# NFC.net
KiCad netlist of a schematic drawn in Altium Designer
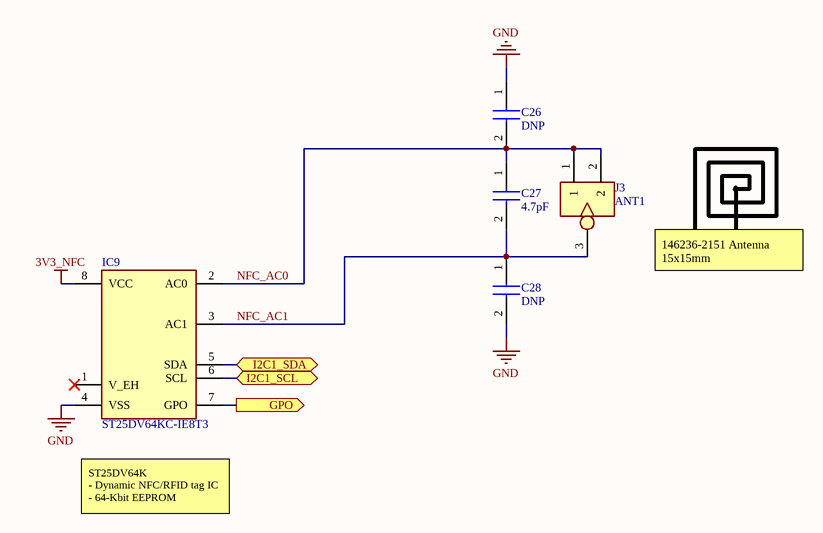
[diagram p0: NFC.SchDoc]

(export (version "E")
  (design (tool "Eeschema 10.0.6"))
  (components
    (comp (ref "C26")
      (value "DNP")
      (footprint "SamacSys:CAPC1005X70N")
      (description "Capacitor")
      (fields
        (field (name "MANUFACTURER_PART_NUMBER") "GRM1555C2A4R7WA01D")
        (field (name "MOUSER PART NUMBER") "81-GRM1555C2A4R7WA1D")
      )
      (libsource (lib "*") (part "GRM1555C2A4R7WA01D"))
    )
    (comp (ref "C27")
      (value "4.7pF")
      (footprint "SamacSys:CAPC1005X70N")
      (description "Capacitor")
      (fields
        (field (name "MANUFACTURER_PART_NUMBER") "GRM1555C2A4R7WA01D")
        (field (name "MOUSER PART NUMBER") "81-GRM1555C2A4R7WA1D")
      )
      (libsource (lib "*") (part "GRM1555C2A4R7WA01D"))
    )
    (comp (ref "C28")
      (value "DNP")
      (footprint "SamacSys:CAPC1005X70N")
      (description "Capacitor")
      (fields
        (field (name "MANUFACTURER_PART_NUMBER") "GRM1555C2A4R7WA01D")
        (field (name "MOUSER PART NUMBER") "81-GRM1555C2A4R7WA1D")
      )
      (libsource (lib "*") (part "GRM1555C2A4R7WA01D"))
    )
    (comp (ref "IC9")
      (value "ST25DV64KC-IE8T3")
      (footprint "SamacSys:SOP65P640X120-8N")
      (description "Integrated Circuit")
      (fields (field (name "MOUSER PART NUMBER") "511-ST25DV64KC-IE8T3"))
      (libsource (lib "SamacSys") (part "ST25DV64KC-IE8T3"))
    )
    (comp (ref "J3")
      (value "ANT1")
      (footprint "SamacSys:RECE.20279.001E.01")
      (description "Connector")
      (fields (field (name "MANUFACTURER_PART_NUMBER") "RECE-20279-001E-01"))
      (libsource (lib "SamacSys") (part "RECE-20279-001E-01"))
    )
  )
  (nets
    (net (code "1") (name "/GPO") (class "Default")
      (node (ref "IC9") (pin "7") (pinfunction "GPO_7") (pintype "open_collector"))
    )
    (net (code "2") (name "/I2C1_SCL") (class "Default")
      (node (ref "IC9") (pin "6") (pinfunction "SCL_6") (pintype "passive"))
    )
    (net (code "3") (name "/I2C1_SDA") (class "Default")
      (node (ref "IC9") (pin "5") (pinfunction "SDA_5") (pintype "passive"))
    )
    (net (code "4") (name "/NFC_AC0") (class "Default")
      (node (ref "C26") (pin "2") (pinfunction "2_2") (pintype "passive"))
      (node (ref "C27") (pin "1") (pinfunction "1_1") (pintype "passive"))
      (node (ref "IC9") (pin "2") (pinfunction "AC0_2") (pintype "passive"))
      (node (ref "J3") (pin "1") (pinfunction "1_1") (pintype "passive"))
      (node (ref "J3") (pin "2") (pinfunction "2_2") (pintype "passive"))
    )
    (net (code "5") (name "/NFC_AC1") (class "Default")
      (node (ref "C27") (pin "2") (pinfunction "2_2") (pintype "passive"))
      (node (ref "C28") (pin "1") (pinfunction "1_1") (pintype "passive"))
      (node (ref "IC9") (pin "3") (pinfunction "AC1_3") (pintype "passive"))
      (node (ref "J3") (pin "3") (pinfunction "3_3") (pintype "passive"))
    )
    (net (code "6") (name "3V3_NFC") (class "Default")
      (node (ref "IC9") (pin "8") (pinfunction "VCC_8") (pintype "passive"))
    )
    (net (code "7") (name "GND") (class "Default")
      (node (ref "C26") (pin "1") (pinfunction "1_1") (pintype "passive"))
      (node (ref "C28") (pin "2") (pinfunction "2_2") (pintype "passive"))
      (node (ref "IC9") (pin "4") (pinfunction "VSS_4") (pintype "passive"))
    )
    (net (code "8") (name "unconnected-(IC9-V_EH-Pad1)") (class "Default")
      (node (ref "IC9") (pin "1") (pinfunction "V_EH_1") (pintype "passive+no_connect"))
    )
  )
)
